# 2_MCU.net
KiCad netlist of a schematic drawn in Altium Designer
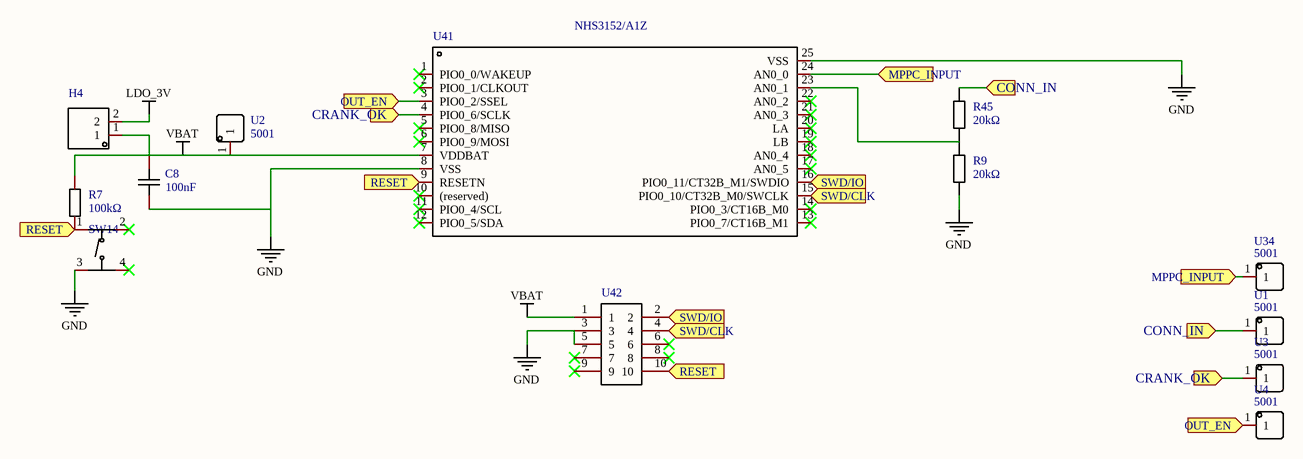
[diagram p0: 2_MCU.schdoc]

(export (version "E")
  (design (tool "Eeschema 10.0.6"))
  (components
    (comp (ref "C8")
      (value "100nF")
      (fields
        (field (name "NAME") "100nF")
        (field (name "MANUFACTURER") "YAGEO")
        (field (name "MANUFACTURER PART") "CC0603KRX7R9BB104")
      )
      (libsource (lib "altium-import") (part "root_3_CC0603KRX7R9BB104_"))
    )
    (comp (ref "H4")
      (value "HDR-M_2.54_1x2P")
      (libsource (lib "altium-import") (part "root_2_HDR-M_2.54_1x2P_"))
    )
    (comp (ref "R7")
      (value "100kΩ")
      (fields
        (field (name "MANUFACTURER") "UNI-ROYAL(厚声)")
        (field (name "MANUFACTURER PART") "0603WAF1003T5E")
        (field (name "TOLERANCE") "±1%")
      )
      (libsource (lib "altium-import") (part "root_3_0603WAF1003T5E_"))
    )
    (comp (ref "R9")
      (value "20kΩ")
      (fields
        (field (name "NAME") "20kΩ")
        (field (name "MANUFACTURER") "UniOhm")
        (field (name "MANUFACTURER PART") "0603WAF2002T5E")
      )
      (libsource (lib "altium-import") (part "root_3_0603WAF2002T5E_"))
    )
    (comp (ref "R45")
      (value "20kΩ")
      (fields
        (field (name "NAME") "20kΩ")
        (field (name "MANUFACTURER") "UniOhm")
        (field (name "MANUFACTURER PART") "0603WAF2002T5E")
      )
      (libsource (lib "altium-import") (part "root_3_0603WAF2002T5E_"))
    )
    (comp (ref "SW14")
      (value "TS-1187A-B-A-B")
      (fields (field (name "MANUFACTURER") "XKB Connectivity(中国星坤)"))
      (libsource (lib "altium-import") (part "root_0_TS-1187A-B-A-B_"))
    )
    (comp (ref "U1")
      (value "5001")
      (fields (field (name "NAME") "5001") (field (name "MANUFACTURER") "Keystone"))
      (libsource (lib "altium-import") (part "root_0_5001_"))
    )
    (comp (ref "U2")
      (value "5001")
      (fields (field (name "NAME") "5001") (field (name "MANUFACTURER") "Keystone"))
      (libsource (lib "altium-import") (part "root_1_5001_"))
    )
    (comp (ref "U3")
      (value "5001")
      (fields (field (name "NAME") "5001") (field (name "MANUFACTURER") "Keystone"))
      (libsource (lib "altium-import") (part "root_0_5001_"))
    )
    (comp (ref "U4")
      (value "5001")
      (fields (field (name "NAME") "5001") (field (name "MANUFACTURER") "Keystone"))
      (libsource (lib "altium-import") (part "root_0_5001_"))
    )
    (comp (ref "U34")
      (value "5001")
      (fields (field (name "NAME") "5001") (field (name "MANUFACTURER") "Keystone"))
      (libsource (lib "altium-import") (part "root_0_5001_"))
    )
    (comp (ref "U41")
      (value "NHS3152/A1Z")
      (fields (field (name "MANUFACTURER") "NXP(恩智浦)") (field (name "MANUFACTURER PART") "NHS3152/A1Z"))
      (libsource (lib "altium-import") (part "root_0_NHS3152/A1Z_"))
    )
    (comp (ref "U42")
      (value "20021121-00010T4LF")
      (fields (field (name "MANUFACTURER") "Amphenol"))
      (libsource (lib "altium-import") (part "root_3_20021121-00010T4LF_"))
    )
  )
  (nets
    (net (code "1") (name "/CONN_IN") (class "Default")
      (node (ref "R45") (pin "1") (pinfunction "1_1") (pintype "passive"))
      (node (ref "U1") (pin "1") (pinfunction "1_1") (pintype "passive"))
    )
    (net (code "2") (name "/CRANK_OK") (class "Default")
      (node (ref "U3") (pin "1") (pinfunction "1_1") (pintype "passive"))
      (node (ref "U41") (pin "4") (pinfunction "PIO0_6/SCLK_4") (pintype "passive"))
    )
    (net (code "3") (name "/MPPC_INPUT") (class "Default")
      (node (ref "U34") (pin "1") (pinfunction "1_1") (pintype "passive"))
      (node (ref "U41") (pin "24") (pinfunction "AN0_0_24") (pintype "passive"))
    )
    (net (code "4") (name "/OUT_EN") (class "Default")
      (node (ref "U4") (pin "1") (pinfunction "1_1") (pintype "passive"))
      (node (ref "U41") (pin "3") (pinfunction "PIO0_2/SSEL_3") (pintype "passive"))
    )
    (net (code "5") (name "/RESET") (class "Default")
      (node (ref "R7") (pin "2") (pinfunction "2_2") (pintype "passive"))
      (node (ref "SW14") (pin "1") (pinfunction "A_1") (pintype "passive"))
      (node (ref "U41") (pin "9") (pinfunction "RESETN_9") (pintype "passive"))
      (node (ref "U42") (pin "10") (pinfunction "10_10") (pintype "passive"))
    )
    (net (code "6") (name "/SWD{slash}CLK") (class "Default")
      (node (ref "U41") (pin "15") (pinfunction "PIO0_10/CT32B_M0/SWCLK_15") (pintype "passive"))
      (node (ref "U42") (pin "4") (pinfunction "4_4") (pintype "passive"))
    )
    (net (code "7") (name "/SWD{slash}IO") (class "Default")
      (node (ref "U41") (pin "16") (pinfunction "PIO0_11/CT32B_M1/SWDIO_16") (pintype "passive"))
      (node (ref "U42") (pin "2") (pinfunction "2_2") (pintype "passive"))
    )
    (net (code "8") (name "GND") (class "Default")
      (node (ref "C8") (pin "2") (pinfunction "2_2") (pintype "passive"))
      (node (ref "R9") (pin "2") (pinfunction "2_2") (pintype "passive"))
      (node (ref "SW14") (pin "3") (pinfunction "C_3") (pintype "passive"))
      (node (ref "U41") (pin "25") (pinfunction "VSS_25") (pintype "passive"))
      (node (ref "U41") (pin "8") (pinfunction "VSS_8") (pintype "passive"))
      (node (ref "U42") (pin "3") (pinfunction "3_3") (pintype "passive"))
      (node (ref "U42") (pin "5") (pinfunction "5_5") (pintype "passive"))
    )
    (net (code "9") (name "LDO_3V") (class "Default")
      (node (ref "H4") (pin "2") (pinfunction "2_2") (pintype "passive"))
    )
    (net (code "10") (name "Net-(U41-AN0_1)") (class "Default")
      (node (ref "R45") (pin "2") (pinfunction "2_2") (pintype "passive"))
      (node (ref "R9") (pin "1") (pinfunction "1_1") (pintype "passive"))
      (node (ref "U41") (pin "23") (pinfunction "AN0_1_23") (pintype "passive"))
    )
    (net (code "11") (name "VBAT") (class "Default")
      (node (ref "C8") (pin "1") (pinfunction "1_1") (pintype "passive"))
      (node (ref "H4") (pin "1") (pinfunction "1_1") (pintype "passive"))
      (node (ref "R7") (pin "1") (pinfunction "1_1") (pintype "passive"))
      (node (ref "U2") (pin "1") (pinfunction "1_1") (pintype "passive"))
      (node (ref "U41") (pin "7") (pinfunction "VDDBAT_7") (pintype "passive"))
      (node (ref "U42") (pin "1") (pinfunction "1_1") (pintype "passive"))
    )
    (net (code "12") (name "unconnected-(SW14-B-Pad2)") (class "Default")
      (node (ref "SW14") (pin "2") (pinfunction "B_2") (pintype "passive+no_connect"))
    )
    (net (code "13") (name "unconnected-(SW14-D-Pad4)") (class "Default")
      (node (ref "SW14") (pin "4") (pinfunction "D_4") (pintype "passive+no_connect"))
    )
    (net (code "14") (name "unconnected-(U41-(reserved)-Pad10)") (class "Default")
      (node (ref "U41") (pin "10") (pinfunction "(reserved)_10") (pintype "passive+no_connect"))
    )
    (net (code "15") (name "unconnected-(U41-AN0_2-Pad22)") (class "Default")
      (node (ref "U41") (pin "22") (pinfunction "AN0_2_22") (pintype "passive+no_connect"))
    )
    (net (code "16") (name "unconnected-(U41-AN0_3-Pad21)") (class "Default")
      (node (ref "U41") (pin "21") (pinfunction "AN0_3_21") (pintype "passive+no_connect"))
    )
    (net (code "17") (name "unconnected-(U41-AN0_4-Pad18)") (class "Default")
      (node (ref "U41") (pin "18") (pinfunction "AN0_4_18") (pintype "passive+no_connect"))
    )
    (net (code "18") (name "unconnected-(U41-AN0_5-Pad17)") (class "Default")
      (node (ref "U41") (pin "17") (pinfunction "AN0_5_17") (pintype "passive+no_connect"))
    )
    (net (code "19") (name "unconnected-(U41-LA-Pad20)") (class "Default")
      (node (ref "U41") (pin "20") (pinfunction "LA_20") (pintype "passive+no_connect"))
    )
    (net (code "20") (name "unconnected-(U41-LB-Pad19)") (class "Default")
      (node (ref "U41") (pin "19") (pinfunction "LB_19") (pintype "passive+no_connect"))
    )
    (net (code "21") (name "unconnected-(U41-PIO0_0{slash}WAKEUP-Pad1)") (class "Default")
      (node (ref "U41") (pin "1") (pinfunction "PIO0_0/WAKEUP_1") (pintype "passive+no_connect"))
    )
    (net (code "22") (name "unconnected-(U41-PIO0_1{slash}CLKOUT-Pad2)") (class "Default")
      (node (ref "U41") (pin "2") (pinfunction "PIO0_1/CLKOUT_2") (pintype "passive+no_connect"))
    )
    (net (code "23") (name "unconnected-(U41-PIO0_3{slash}CT16B_M0-Pad14)") (class "Default")
      (node (ref "U41") (pin "14") (pinfunction "PIO0_3/CT16B_M0_14") (pintype "passive+no_connect"))
    )
    (net (code "24") (name "unconnected-(U41-PIO0_4{slash}SCL-Pad11)") (class "Default")
      (node (ref "U41") (pin "11") (pinfunction "PIO0_4/SCL_11") (pintype "passive+no_connect"))
    )
    (net (code "25") (name "unconnected-(U41-PIO0_5{slash}SDA-Pad12)") (class "Default")
      (node (ref "U41") (pin "12") (pinfunction "PIO0_5/SDA_12") (pintype "passive+no_connect"))
    )
    (net (code "26") (name "unconnected-(U41-PIO0_7{slash}CT16B_M1-Pad13)") (class "Default")
      (node (ref "U41") (pin "13") (pinfunction "PIO0_7/CT16B_M1_13") (pintype "passive+no_connect"))
    )
    (net (code "27") (name "unconnected-(U41-PIO0_8{slash}MISO-Pad5)") (class "Default")
      (node (ref "U41") (pin "5") (pinfunction "PIO0_8/MISO_5") (pintype "passive+no_connect"))
    )
    (net (code "28") (name "unconnected-(U41-PIO0_9{slash}MOSI-Pad6)") (class "Default")
      (node (ref "U41") (pin "6") (pinfunction "PIO0_9/MOSI_6") (pintype "passive+no_connect"))
    )
    (net (code "29") (name "unconnected-(U42-Pad6)") (class "Default")
      (node (ref "U42") (pin "6") (pinfunction "6_6") (pintype "passive+no_connect"))
    )
    (net (code "30") (name "unconnected-(U42-Pad7)") (class "Default")
      (node (ref "U42") (pin "7") (pinfunction "7_7") (pintype "passive+no_connect"))
    )
    (net (code "31") (name "unconnected-(U42-Pad8)") (class "Default")
      (node (ref "U42") (pin "8") (pinfunction "8_8") (pintype "passive+no_connect"))
    )
    (net (code "32") (name "unconnected-(U42-Pad9)") (class "Default")
      (node (ref "U42") (pin "9") (pinfunction "9_9") (pintype "passive+no_connect"))
    )
  )
)
